# subckt_buffered_tia_dual.net
KiCad netlist of a schematic drawn in Altium Designer
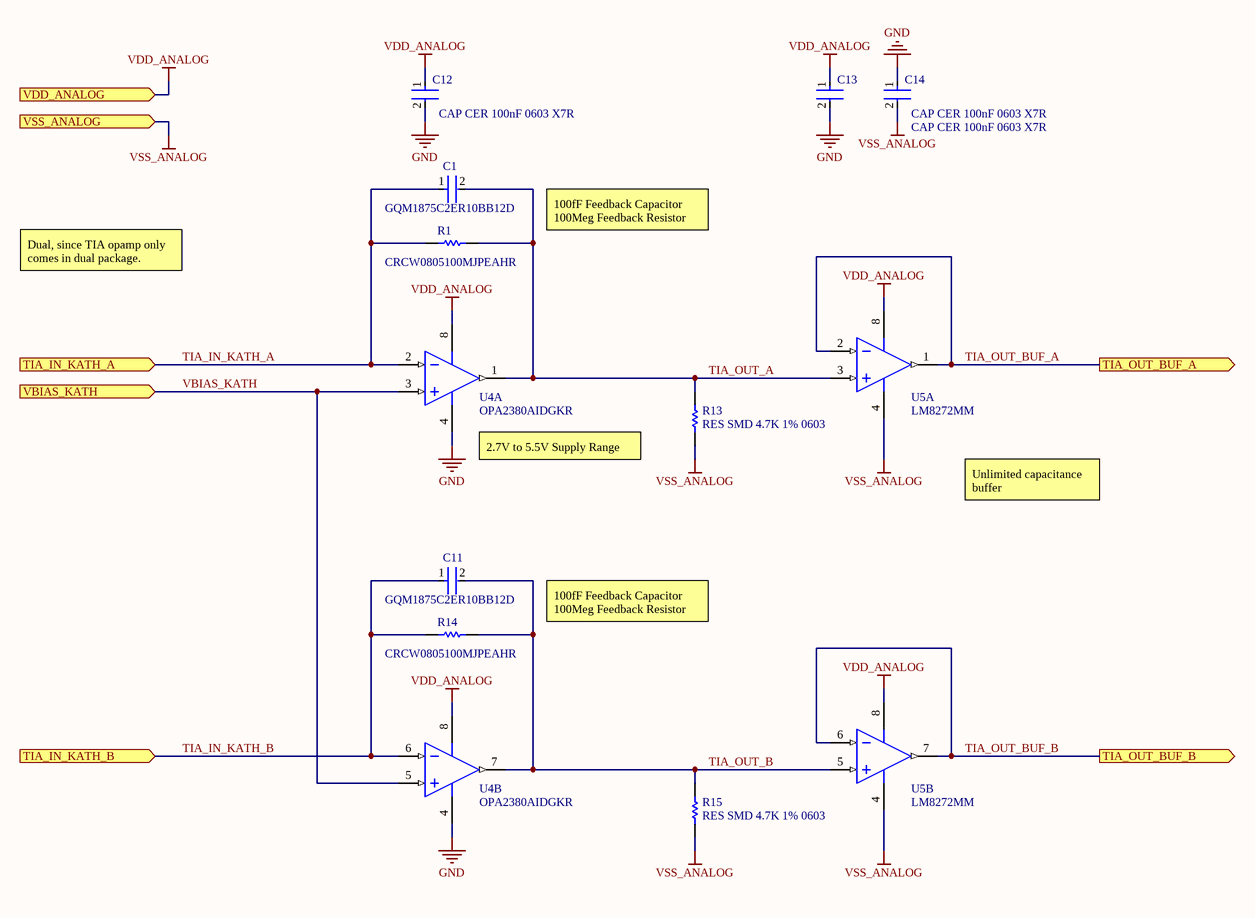
[diagram p0: subckt_buffered_tia_dual.SchDoc]

(export (version "E")
  (design (tool "Eeschema 10.0.6"))
  (components
    (comp (ref "C1")
      (value "GQM1875C2ER10BB12D")
      (footprint "FP-GQM187-0_15-MFG")
      (description "Ceramic Capacitor 0.1pF ±0.1pF 250VDC C0G 0603 Paper T/R")
      (libsource (lib "Altium Content Vault") (part "02cd4be3c70576c341d710602a673aa"))
    )
    (comp (ref "C11")
      (value "GQM1875C2ER10BB12D")
      (footprint "FP-GQM187-0_15-MFG")
      (description "Ceramic Capacitor 0.1pF ±0.1pF 250VDC C0G 0603 Paper T/R")
      (libsource (lib "Altium Content Vault") (part "02cd4be3c70576c341d710602a673aa"))
    )
    (comp (ref "C12")
      (value "CAP CER 100nF 0603 X7R")
      (footprint "FP-CC0603-DA-MFG")
      (description "CAP CER 0.1UF 16V X7R 0603")
      (fields
        (field (name "OCTOPART") "https://octopart.com/cc0603krx7r7bb104-yageo-192941")
        (field (name "TOLERANCE") "0.1")
      )
      (libsource (lib "Altium Content Vault") (part "11868f565c42a9108669ba33697ecf6"))
    )
    (comp (ref "C13")
      (value "CAP CER 100nF 0603 X7R")
      (footprint "FP-CC0603-DA-MFG")
      (description "CAP CER 0.1UF 16V X7R 0603")
      (fields
        (field (name "OCTOPART") "https://octopart.com/cc0603krx7r7bb104-yageo-192941")
        (field (name "TOLERANCE") "0.1")
      )
      (libsource (lib "Altium Content Vault") (part "11868f565c42a9108669ba33697ecf6"))
    )
    (comp (ref "C14")
      (value "CAP CER 100nF 0603 X7R")
      (footprint "FP-CC0603-DA-MFG")
      (description "CAP CER 0.1UF 16V X7R 0603")
      (fields
        (field (name "OCTOPART") "https://octopart.com/cc0603krx7r7bb104-yageo-192941")
        (field (name "TOLERANCE") "0.1")
      )
      (libsource (lib "Altium Content Vault") (part "11868f565c42a9108669ba33697ecf6"))
    )
    (comp (ref "R1")
      (value "CRCW0805100MJPEAHR")
      (footprint "RESC2013X50X30NL20T20")
      (fields (field (name "MANUFACTURER") "Vishay Dale"))
      (libsource (lib "Altium Content Vault") (part "RES"))
    )
    (comp (ref "R13")
      (value "RES SMD 4.7K 1% 0603")
      (footprint "RESC1609X55X30LL15T15")
      (description "Chip Resistor, 10 KOhm, +/- 1%, 0.1 W, -55 to 155 degC, 0603 (1608 Metric), RoHS, Tape and Reel")
      (fields (field (name "TOLERANCE") "1%") (field (name "MANUFACTURER") "Panasonic"))
      (libsource (lib "Altium Content Vault") (part "RES-2"))
    )
    (comp (ref "R14")
      (value "CRCW0805100MJPEAHR")
      (footprint "RESC2013X50X30NL20T20")
      (fields (field (name "MANUFACTURER") "Vishay Dale"))
      (libsource (lib "Altium Content Vault") (part "RES"))
    )
    (comp (ref "R15")
      (value "RES SMD 4.7K 1% 0603")
      (footprint "RESC1609X55X30LL15T15")
      (description "Chip Resistor, 10 KOhm, +/- 1%, 0.1 W, -55 to 155 degC, 0603 (1608 Metric), RoHS, Tape and Reel")
      (fields (field (name "TOLERANCE") "1%") (field (name "MANUFACTURER") "Panasonic"))
      (libsource (lib "Altium Content Vault") (part "RES-2"))
    )
    (comp (ref "U4")
      (value "OPA2380AIDGKR")
      (footprint "DGK0008A_N")
      (fields (field (name "MANUFACTURER") "Texas Instruments"))
      (libsource (lib "Altium Content Vault") (part "TI-OPA2380DGK8"))
    )
    (comp (ref "U5")
      (value "LM8272MM")
      (footprint "DGK0008A_L")
      (description "RRIO, High Output Current & Unlimited Cap Load Op Amp, 8-pin Mini SOIC")
      (fields (field (name "MANUFACTURER") "Texas Instruments"))
      (libsource (lib "Altium Content Vault") (part "AMP-OPA-LM6132-8"))
    )
  )
  (nets
    (net (code "1") (name "/TIA_IN_KATH_A") (class "Default")
      (node (ref "C1") (pin "1") (pinfunction "1_1") (pintype "passive"))
      (node (ref "R1") (pin "1") (pinfunction "1_1") (pintype "passive"))
      (node (ref "U4") (pin "2") (pinfunction "IN_A-_2") (pintype "input"))
    )
    (net (code "2") (name "/TIA_IN_KATH_B") (class "Default")
      (node (ref "C11") (pin "1") (pinfunction "1_1") (pintype "passive"))
      (node (ref "R14") (pin "1") (pinfunction "1_1") (pintype "passive"))
      (node (ref "U4") (pin "6") (pinfunction "IN_B-_6") (pintype "input"))
    )
    (net (code "3") (name "/TIA_OUT_A") (class "Default")
      (node (ref "C1") (pin "2") (pinfunction "2_2") (pintype "passive"))
      (node (ref "R1") (pin "2") (pinfunction "2_2") (pintype "passive"))
      (node (ref "R13") (pin "2") (pinfunction "2_2") (pintype "passive"))
      (node (ref "U4") (pin "1") (pinfunction "OUT_A_1") (pintype "output"))
      (node (ref "U5") (pin "3") (pinfunction "INA+_3") (pintype "input"))
    )
    (net (code "4") (name "/TIA_OUT_B") (class "Default")
      (node (ref "C11") (pin "2") (pinfunction "2_2") (pintype "passive"))
      (node (ref "R14") (pin "2") (pinfunction "2_2") (pintype "passive"))
      (node (ref "R15") (pin "2") (pinfunction "2_2") (pintype "passive"))
      (node (ref "U4") (pin "7") (pinfunction "OUT_B_7") (pintype "output"))
      (node (ref "U5") (pin "5") (pinfunction "INB+_5") (pintype "input"))
    )
    (net (code "5") (name "/TIA_OUT_BUF_A") (class "Default")
      (node (ref "U5") (pin "1") (pinfunction "OUTA_1") (pintype "output"))
      (node (ref "U5") (pin "2") (pinfunction "INA-_2") (pintype "input"))
    )
    (net (code "6") (name "/TIA_OUT_BUF_B") (class "Default")
      (node (ref "U5") (pin "6") (pinfunction "INB-_6") (pintype "input"))
      (node (ref "U5") (pin "7") (pinfunction "OUTB_7") (pintype "output"))
    )
    (net (code "7") (name "/VBIAS_KATH") (class "Default")
      (node (ref "U4") (pin "3") (pinfunction "IN_A+_3") (pintype "input"))
      (node (ref "U4") (pin "5") (pinfunction "IN_B+_5") (pintype "input"))
    )
    (net (code "8") (name "GND") (class "Default")
      (node (ref "C12") (pin "2") (pinfunction "2_2") (pintype "passive"))
      (node (ref "C13") (pin "2") (pinfunction "2_2") (pintype "passive"))
      (node (ref "C14") (pin "1") (pinfunction "1_1") (pintype "passive"))
      (node (ref "U4") (pin "4") (pinfunction "V-_4") (pintype "power_in"))
    )
    (net (code "9") (name "VDD_ANALOG") (class "Default")
      (node (ref "C12") (pin "1") (pinfunction "1_1") (pintype "passive"))
      (node (ref "C13") (pin "1") (pinfunction "1_1") (pintype "passive"))
      (node (ref "U4") (pin "8") (pinfunction "V+_8") (pintype "power_in"))
      (node (ref "U5") (pin "8") (pinfunction "V+_8") (pintype "power_in"))
    )
    (net (code "10") (name "VSS_ANALOG") (class "Default")
      (node (ref "C14") (pin "2") (pinfunction "2_2") (pintype "passive"))
      (node (ref "R13") (pin "1") (pinfunction "1_1") (pintype "passive"))
      (node (ref "R15") (pin "1") (pinfunction "1_1") (pintype "passive"))
      (node (ref "U5") (pin "4") (pinfunction "V-_4") (pintype "power_in"))
    )
  )
)
